# TM7705.net
KiCad netlist of a schematic drawn in Altium Designer
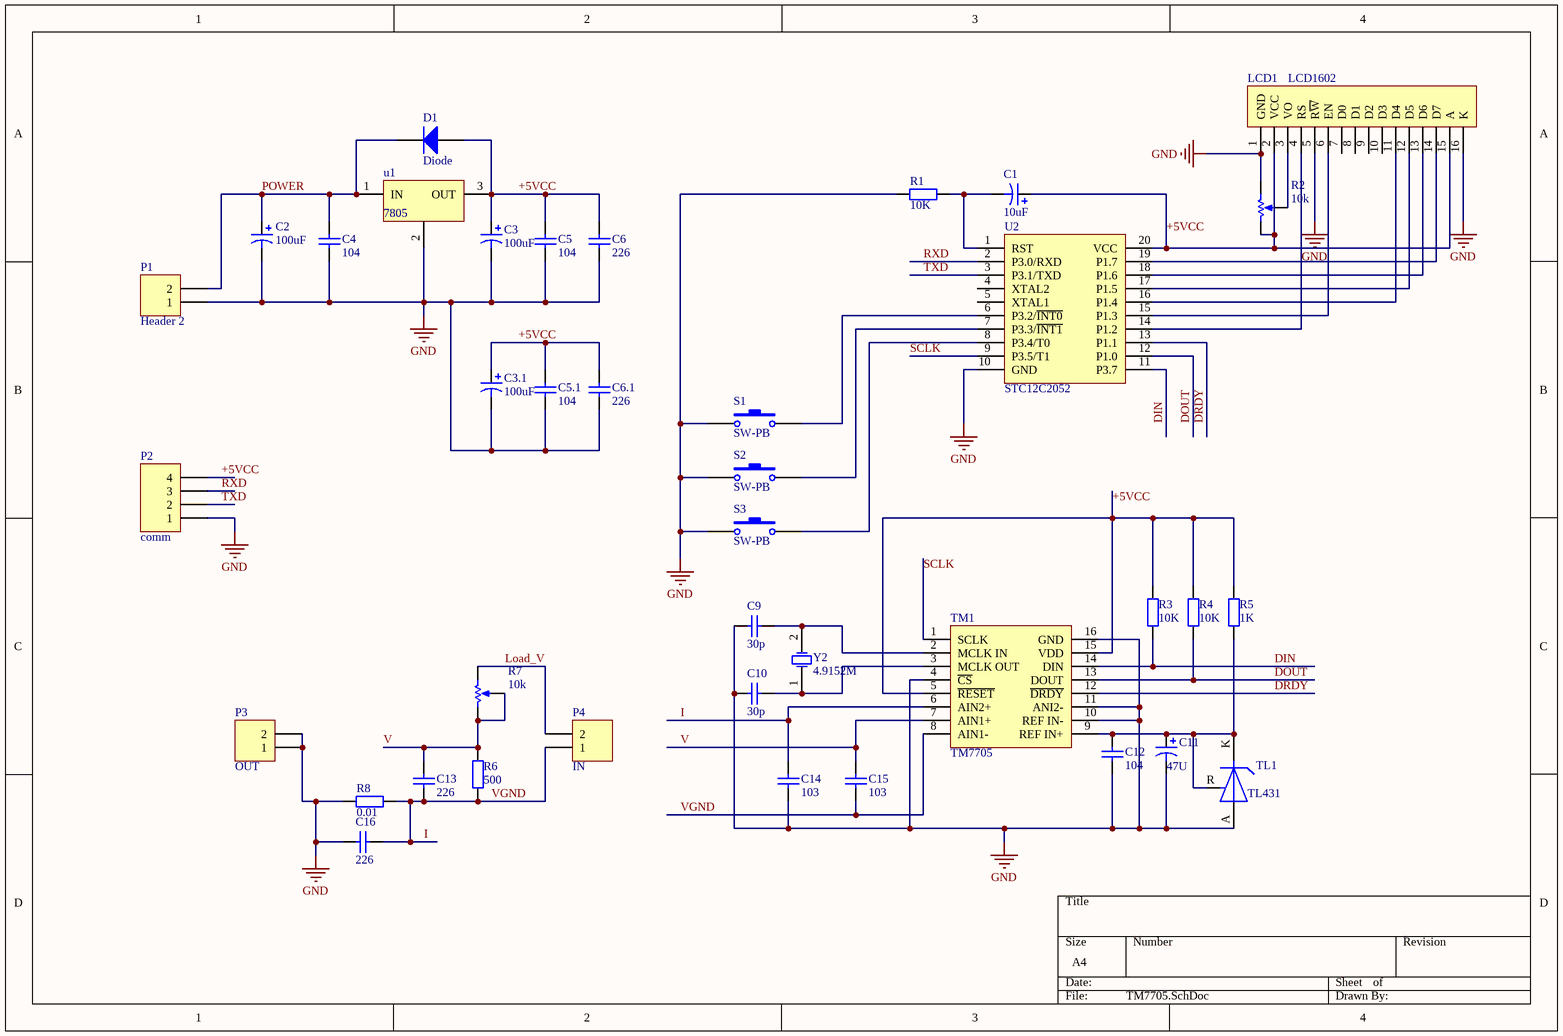
[diagram p0: TM7705.SchDoc]

(export (version "E")
  (design (tool "Eeschema 10.0.6"))
  (components
    (comp (ref "C1")
      (value "10uF")
      (footprint "0805")
      (description "Polarized Capacitor (Radial)")
      (fields (field (name "PUBLISHER") "Altium Limited"))
      (libsource (lib "Miscellaneous Devices") (part "Cap Pol1"))
    )
    (comp (ref "C2")
      (value "100uF")
      (footprint "DR3")
      (description "Polarized Capacitor (Radial)")
      (fields (field (name "PUBLISHER") "Altium Limited"))
      (libsource (lib "Miscellaneous Devices") (part "Cap Pol1"))
    )
    (comp (ref "C3")
      (value "100uF")
      (footprint "DR")
      (description "Polarized Capacitor (Radial)")
      (fields (field (name "PUBLISHER") "Altium Limited"))
      (libsource (lib "Miscellaneous Devices") (part "Cap Pol1"))
    )
    (comp (ref "C3.1")
      (value "100uF")
      (footprint "DR")
      (description "Polarized Capacitor (Radial)")
      (fields (field (name "PUBLISHER") "Altium Limited"))
      (libsource (lib "Miscellaneous Devices") (part "Cap Pol1"))
    )
    (comp (ref "C4")
      (value "104")
      (footprint "0805C")
      (description "Capacitor")
      (fields (field (name "PUBLISHER") "Altium Limited"))
      (libsource (lib "Miscellaneous Devices") (part "Cap"))
    )
    (comp (ref "C5")
      (value "104")
      (footprint "0805C")
      (description "Capacitor")
      (fields (field (name "PUBLISHER") "Altium Limited"))
      (libsource (lib "Miscellaneous Devices") (part "Cap"))
    )
    (comp (ref "C5.1")
      (value "104")
      (footprint "0805C")
      (description "Capacitor")
      (fields (field (name "PUBLISHER") "Altium Limited"))
      (libsource (lib "Miscellaneous Devices") (part "Cap"))
    )
    (comp (ref "C6")
      (value "226")
      (footprint "0805C")
      (description "Capacitor")
      (fields (field (name "PUBLISHER") "Altium Limited"))
      (libsource (lib "Miscellaneous Devices") (part "Cap"))
    )
    (comp (ref "C6.1")
      (value "226")
      (footprint "0805C")
      (description "Capacitor")
      (fields (field (name "PUBLISHER") "Altium Limited"))
      (libsource (lib "Miscellaneous Devices") (part "Cap"))
    )
    (comp (ref "C9")
      (value "30p")
      (footprint "0805C")
      (description "Capacitor")
      (fields (field (name "PUBLISHER") "Altium Limited"))
      (libsource (lib "Miscellaneous Devices") (part "Cap"))
    )
    (comp (ref "C10")
      (value "30p")
      (footprint "0805C")
      (description "Capacitor")
      (fields (field (name "PUBLISHER") "Altium Limited"))
      (libsource (lib "Miscellaneous Devices") (part "Cap"))
    )
    (comp (ref "C11")
      (value "47U")
      (footprint "DR")
      (description "Polarized Capacitor (Radial)")
      (fields (field (name "PUBLISHER") "Altium Limited"))
      (libsource (lib "Miscellaneous Devices") (part "Cap Pol1"))
    )
    (comp (ref "C12")
      (value "104")
      (footprint "0805C")
      (description "Capacitor")
      (fields (field (name "PUBLISHER") "Altium Limited"))
      (libsource (lib "Miscellaneous Devices") (part "Cap"))
    )
    (comp (ref "C13")
      (value "226")
      (footprint "0805C")
      (description "Capacitor")
      (fields (field (name "PUBLISHER") "Altium Limited"))
      (libsource (lib "Miscellaneous Devices") (part "Cap"))
    )
    (comp (ref "C14")
      (value "103")
      (footprint "0805C")
      (description "Capacitor")
      (fields (field (name "PUBLISHER") "Altium Limited"))
      (libsource (lib "Miscellaneous Devices") (part "Cap"))
    )
    (comp (ref "C15")
      (value "103")
      (footprint "0805C")
      (description "Capacitor")
      (fields (field (name "PUBLISHER") "Altium Limited"))
      (libsource (lib "Miscellaneous Devices") (part "Cap"))
    )
    (comp (ref "C16")
      (value "226")
      (footprint "0805C")
      (description "Capacitor")
      (fields (field (name "PUBLISHER") "Altium Limited"))
      (libsource (lib "Miscellaneous Devices") (part "Cap"))
    )
    (comp (ref "D1")
      (value "Diode")
      (footprint "DO-214AC")
      (description "Default Diode")
      (fields (field (name "PUBLISHER") "Altium Limited"))
      (libsource (lib "Miscellaneous Devices") (part "Diode"))
    )
    (comp (ref "LCD1") (value "LCD1602") (footprint "LCD1602") (libsource (lib "Sch库") (part "LCD1602")))
    (comp (ref "P1")
      (value "Header 2")
      (footprint "HDR1X2")
      (description "Header, 2-Pin")
      (fields (field (name "PUBLISHER") "Altium Limited"))
      (libsource (lib "Miscellaneous Connectors") (part "Header 2"))
    )
    (comp (ref "P2")
      (value "comm")
      (footprint "HDR1X4")
      (description "Header, 4-Pin")
      (fields (field (name "PUBLISHER") "Altium Limited"))
      (libsource (lib "Miscellaneous Connectors") (part "Header 4"))
    )
    (comp (ref "P3")
      (value "OUT")
      (footprint "HDR1X2")
      (description "Header, 2-Pin")
      (fields (field (name "PUBLISHER") "Altium Limited"))
      (libsource (lib "Miscellaneous Connectors") (part "Header 2"))
    )
    (comp (ref "P4")
      (value "IN")
      (footprint "HDR1X2")
      (description "Header, 2-Pin")
      (fields (field (name "PUBLISHER") "Altium Limited"))
      (libsource (lib "") (part "Header 2_1"))
    )
    (comp (ref "R1")
      (value "10K")
      (footprint "0805R")
      (description "Resistor")
      (fields (field (name "PUBLISHER") "Altium Limited"))
      (libsource (lib "") (part "Res2_1"))
    )
    (comp (ref "R2")
      (value "10k")
      (footprint "DWQ")
      (description "Potentiometer")
      (fields (field (name "PUBLISHER") "Altium Limited"))
      (libsource (lib "Miscellaneous Devices") (part "RPot"))
    )
    (comp (ref "R3")
      (value "10K")
      (footprint "0805R")
      (description "Resistor")
      (fields (field (name "PUBLISHER") "Altium Limited"))
      (libsource (lib "Miscellaneous Devices") (part "Res2"))
    )
    (comp (ref "R4")
      (value "10K")
      (footprint "0805R")
      (description "Resistor")
      (fields (field (name "PUBLISHER") "Altium Limited"))
      (libsource (lib "Miscellaneous Devices") (part "Res2"))
    )
    (comp (ref "R5")
      (value "1K")
      (footprint "0805R")
      (description "Resistor")
      (fields (field (name "PUBLISHER") "Altium Limited"))
      (libsource (lib "Miscellaneous Devices") (part "Res2"))
    )
    (comp (ref "R6")
      (value "500")
      (footprint "0805R")
      (description "Resistor")
      (fields (field (name "PUBLISHER") "Altium Limited"))
      (libsource (lib "") (part "Res2_2"))
    )
    (comp (ref "R7")
      (value "10k")
      (footprint "DWQ1")
      (description "Potentiometer")
      (fields (field (name "PUBLISHER") "Altium Limited"))
      (libsource (lib "Miscellaneous Devices") (part "RPot"))
    )
    (comp (ref "R8")
      (value "0.01")
      (footprint "DZ-1W")
      (description "Resistor")
      (fields (field (name "PUBLISHER") "Altium Limited"))
      (libsource (lib "") (part "Res2_1"))
    )
    (comp (ref "S1")
      (value "SW-PB")
      (footprint "SW")
      (description "Switch")
      (fields (field (name "PUBLISHER") "Altium Limited"))
      (libsource (lib "Miscellaneous Devices") (part "SW-PB"))
    )
    (comp (ref "S2")
      (value "SW-PB")
      (footprint "SW")
      (description "Switch")
      (fields (field (name "PUBLISHER") "Altium Limited"))
      (libsource (lib "Miscellaneous Devices") (part "SW-PB"))
    )
    (comp (ref "S3")
      (value "SW-PB")
      (footprint "SW")
      (description "Switch")
      (fields (field (name "PUBLISHER") "Altium Limited"))
      (libsource (lib "Miscellaneous Devices") (part "SW-PB"))
    )
    (comp (ref "TL1") (value "TL431") (footprint "TL431") (libsource (lib "Sch库") (part "TL431")))
    (comp (ref "TM1") (value "TM7705") (footprint "SOIC-16") (libsource (lib "Schlib1") (part "TM7705")))
    (comp (ref "u1") (value "7805") (footprint "DPAK") (libsource (lib "Schlib1") (part "7805")))
    (comp (ref "U2") (value "STC12C2052") (footprint "SOIC-20") (libsource (lib "Sch库") (part "STC12C2052")))
    (comp (ref "Y2")
      (value "4.9152M")
      (footprint "JZ")
      (description "Crystal Oscillator")
      (fields (field (name "PUBLISHER") "Altium Limited"))
      (libsource (lib "Miscellaneous Devices") (part "XTAL"))
    )
  )
  (nets
    (net (code "1") (name "/+5VCC") (class "Default")
      (node (ref "C1") (pin "1") (pinfunction "1_1") (pintype "passive"))
      (node (ref "C3") (pin "1") (pinfunction "1_1") (pintype "passive"))
      (node (ref "C3.1") (pin "1") (pinfunction "1_1") (pintype "passive"))
      (node (ref "C5") (pin "2") (pinfunction "2_2") (pintype "passive"))
      (node (ref "C5.1") (pin "2") (pinfunction "2_2") (pintype "passive"))
      (node (ref "C6") (pin "2") (pinfunction "2_2") (pintype "passive"))
      (node (ref "C6.1") (pin "2") (pinfunction "2_2") (pintype "passive"))
      (node (ref "D1") (pin "1") (pinfunction "A_1") (pintype "passive"))
      (node (ref "LCD1") (pin "15") (pinfunction "A_15") (pintype "passive"))
      (node (ref "LCD1") (pin "2") (pinfunction "VCC_2") (pintype "passive"))
      (node (ref "P2") (pin "4") (pinfunction "4_4") (pintype "passive"))
      (node (ref "R2") (pin "2") (pinfunction "BOT_2") (pintype "passive"))
      (node (ref "R3") (pin "2") (pinfunction "2_2") (pintype "passive"))
      (node (ref "R4") (pin "2") (pinfunction "2_2") (pintype "passive"))
      (node (ref "R5") (pin "2") (pinfunction "2_2") (pintype "passive"))
      (node (ref "TM1") (pin "15") (pinfunction "VDD_15") (pintype "passive"))
      (node (ref "TM1") (pin "5") (pinfunction "~{RESET}_5") (pintype "passive"))
      (node (ref "U2") (pin "20") (pinfunction "VCC_20") (pintype "passive"))
      (node (ref "u1") (pin "3") (pinfunction "OUT_3") (pintype "passive"))
    )
    (net (code "2") (name "/DIN") (class "Default")
      (node (ref "R3") (pin "1") (pinfunction "1_1") (pintype "passive"))
      (node (ref "TM1") (pin "14") (pinfunction "DIN_14") (pintype "passive"))
      (node (ref "U2") (pin "11") (pinfunction "P3.7_11") (pintype "passive"))
    )
    (net (code "3") (name "/DOUT") (class "Default")
      (node (ref "R4") (pin "1") (pinfunction "1_1") (pintype "passive"))
      (node (ref "TM1") (pin "13") (pinfunction "DOUT_13") (pintype "passive"))
      (node (ref "U2") (pin "12") (pinfunction "P1.0_12") (pintype "passive"))
    )
    (net (code "4") (name "/DRDY") (class "Default")
      (node (ref "TM1") (pin "12") (pinfunction "~{DRDY}_12") (pintype "passive"))
      (node (ref "U2") (pin "13") (pinfunction "P1.1_13") (pintype "passive"))
    )
    (net (code "5") (name "/I") (class "Default")
      (node (ref "C13") (pin "1") (pinfunction "1_1") (pintype "passive"))
      (node (ref "C14") (pin "2") (pinfunction "2_2") (pintype "passive"))
      (node (ref "C15") (pin "1") (pinfunction "1_1") (pintype "passive"))
      (node (ref "C16") (pin "1") (pinfunction "1_1") (pintype "passive"))
      (node (ref "P4") (pin "1") (pinfunction "1_1") (pintype "passive"))
      (node (ref "R6") (pin "1") (pinfunction "1_1") (pintype "passive"))
      (node (ref "R8") (pin "1") (pinfunction "1_1") (pintype "passive"))
      (node (ref "TM1") (pin "6") (pinfunction "AIN2+_6") (pintype "passive"))
      (node (ref "TM1") (pin "8") (pinfunction "AIN1-_8") (pintype "passive"))
    )
    (net (code "6") (name "/Load_V") (class "Default")
      (node (ref "P4") (pin "2") (pinfunction "2_2") (pintype "passive"))
      (node (ref "R7") (pin "1") (pinfunction "TOP_1") (pintype "passive"))
    )
    (net (code "7") (name "/POWER") (class "Default")
      (node (ref "C2") (pin "1") (pinfunction "1_1") (pintype "passive"))
      (node (ref "C4") (pin "2") (pinfunction "2_2") (pintype "passive"))
      (node (ref "D1") (pin "2") (pinfunction "K_2") (pintype "passive"))
      (node (ref "P1") (pin "2") (pinfunction "2_2") (pintype "passive"))
      (node (ref "u1") (pin "1") (pinfunction "IN_1") (pintype "passive"))
    )
    (net (code "8") (name "/RXD") (class "Default")
      (node (ref "P2") (pin "3") (pinfunction "3_3") (pintype "passive"))
      (node (ref "U2") (pin "2") (pinfunction "P3.0/RXD_2") (pintype "passive"))
    )
    (net (code "9") (name "/SCLK") (class "Default")
      (node (ref "TM1") (pin "1") (pinfunction "SCLK_1") (pintype "passive"))
      (node (ref "U2") (pin "9") (pinfunction "P3.5/T1_9") (pintype "passive"))
    )
    (net (code "10") (name "/TXD") (class "Default")
      (node (ref "P2") (pin "2") (pinfunction "2_2") (pintype "passive"))
      (node (ref "U2") (pin "3") (pinfunction "P3.1/TXD_3") (pintype "passive"))
    )
    (net (code "11") (name "/V") (class "Default")
      (node (ref "C13") (pin "2") (pinfunction "2_2") (pintype "passive"))
      (node (ref "C15") (pin "2") (pinfunction "2_2") (pintype "passive"))
      (node (ref "R6") (pin "2") (pinfunction "2_2") (pintype "passive"))
      (node (ref "R7") (pin "2") (pinfunction "BOT_2") (pintype "passive"))
      (node (ref "R7") (pin "3") (pinfunction "TAP_3") (pintype "passive"))
      (node (ref "TM1") (pin "7") (pinfunction "AIN1+_7") (pintype "passive"))
    )
    (net (code "12") (name "GND") (class "Default")
      (node (ref "C10") (pin "1") (pinfunction "1_1") (pintype "passive"))
      (node (ref "C11") (pin "2") (pinfunction "2_2") (pintype "passive"))
      (node (ref "C12") (pin "1") (pinfunction "1_1") (pintype "passive"))
      (node (ref "C14") (pin "1") (pinfunction "1_1") (pintype "passive"))
      (node (ref "C16") (pin "2") (pinfunction "2_2") (pintype "passive"))
      (node (ref "C2") (pin "2") (pinfunction "2_2") (pintype "passive"))
      (node (ref "C3") (pin "2") (pinfunction "2_2") (pintype "passive"))
      (node (ref "C3.1") (pin "2") (pinfunction "2_2") (pintype "passive"))
      (node (ref "C4") (pin "1") (pinfunction "1_1") (pintype "passive"))
      (node (ref "C5") (pin "1") (pinfunction "1_1") (pintype "passive"))
      (node (ref "C5.1") (pin "1") (pinfunction "1_1") (pintype "passive"))
      (node (ref "C6") (pin "1") (pinfunction "1_1") (pintype "passive"))
      (node (ref "C6.1") (pin "1") (pinfunction "1_1") (pintype "passive"))
      (node (ref "C9") (pin "1") (pinfunction "1_1") (pintype "passive"))
      (node (ref "LCD1") (pin "1") (pinfunction "GND_1") (pintype "passive"))
      (node (ref "LCD1") (pin "16") (pinfunction "K_16") (pintype "passive"))
      (node (ref "LCD1") (pin "5") (pinfunction "R~{W}_5") (pintype "passive"))
      (node (ref "P1") (pin "1") (pinfunction "1_1") (pintype "passive"))
      (node (ref "P2") (pin "1") (pinfunction "1_1") (pintype "passive"))
      (node (ref "P3") (pin "1") (pinfunction "1_1") (pintype "passive"))
      (node (ref "P3") (pin "2") (pinfunction "2_2") (pintype "passive"))
      (node (ref "R1") (pin "2") (pinfunction "2_2") (pintype "passive"))
      (node (ref "R2") (pin "1") (pinfunction "TOP_1") (pintype "passive"))
      (node (ref "R8") (pin "2") (pinfunction "2_2") (pintype "passive"))
      (node (ref "S1") (pin "1") (pinfunction "1_1") (pintype "passive"))
      (node (ref "S2") (pin "1") (pinfunction "1_1") (pintype "passive"))
      (node (ref "S3") (pin "1") (pinfunction "1_1") (pintype "passive"))
      (node (ref "TL1") (pin "A") (pinfunction "A_A") (pintype "passive"))
      (node (ref "TM1") (pin "10") (pinfunction "REF_IN-_10") (pintype "passive"))
      (node (ref "TM1") (pin "11") (pinfunction "ANI2-_11") (pintype "passive"))
      (node (ref "TM1") (pin "16") (pinfunction "GND_16") (pintype "passive"))
      (node (ref "TM1") (pin "4") (pinfunction "~{CS}_4") (pintype "passive"))
      (node (ref "U2") (pin "10") (pinfunction "GND_10") (pintype "passive"))
      (node (ref "u1") (pin "2") (pinfunction "GND_2") (pintype "passive"))
    )
    (net (code "13") (name "Net-(LCD1-D4)") (class "Default")
      (node (ref "LCD1") (pin "11") (pinfunction "D4_11") (pintype "passive"))
      (node (ref "U2") (pin "16") (pinfunction "P1.4_16") (pintype "passive"))
    )
    (net (code "14") (name "Net-(LCD1-D5)") (class "Default")
      (node (ref "LCD1") (pin "12") (pinfunction "D5_12") (pintype "passive"))
      (node (ref "U2") (pin "17") (pinfunction "P1.5_17") (pintype "passive"))
    )
    (net (code "15") (name "Net-(LCD1-D6)") (class "Default")
      (node (ref "LCD1") (pin "13") (pinfunction "D6_13") (pintype "passive"))
      (node (ref "U2") (pin "18") (pinfunction "P1.6_18") (pintype "passive"))
    )
    (net (code "16") (name "Net-(LCD1-D7)") (class "Default")
      (node (ref "LCD1") (pin "14") (pinfunction "D7_14") (pintype "passive"))
      (node (ref "U2") (pin "19") (pinfunction "P1.7_19") (pintype "passive"))
    )
    (net (code "17") (name "Net-(LCD1-EN)") (class "Default")
      (node (ref "LCD1") (pin "6") (pinfunction "EN_6") (pintype "passive"))
      (node (ref "U2") (pin "15") (pinfunction "P1.3_15") (pintype "passive"))
    )
    (net (code "18") (name "Net-(LCD1-RS)") (class "Default")
      (node (ref "LCD1") (pin "4") (pinfunction "RS_4") (pintype "passive"))
      (node (ref "U2") (pin "14") (pinfunction "P1.2_14") (pintype "passive"))
    )
    (net (code "19") (name "Net-(LCD1-VO)") (class "Default")
      (node (ref "LCD1") (pin "3") (pinfunction "VO_3") (pintype "passive"))
      (node (ref "R2") (pin "3") (pinfunction "TAP_3") (pintype "passive"))
    )
    (net (code "20") (name "Net-(TM1-MCLK_IN)") (class "Default")
      (node (ref "C9") (pin "2") (pinfunction "2_2") (pintype "passive"))
      (node (ref "TM1") (pin "2") (pinfunction "MCLK_IN_2") (pintype "passive"))
      (node (ref "Y2") (pin "2") (pinfunction "OSC2_2") (pintype "passive"))
    )
    (net (code "21") (name "Net-(TM1-MCLK_OUT)") (class "Default")
      (node (ref "C10") (pin "2") (pinfunction "2_2") (pintype "passive"))
      (node (ref "TM1") (pin "3") (pinfunction "MCLK_OUT_3") (pintype "passive"))
      (node (ref "Y2") (pin "1") (pinfunction "OSC1_1") (pintype "passive"))
    )
    (net (code "22") (name "Net-(TM1-REF_IN+)") (class "Default")
      (node (ref "C11") (pin "1") (pinfunction "1_1") (pintype "passive"))
      (node (ref "C12") (pin "2") (pinfunction "2_2") (pintype "passive"))
      (node (ref "R5") (pin "1") (pinfunction "1_1") (pintype "passive"))
      (node (ref "TL1") (pin "K") (pinfunction "K_K") (pintype "passive"))
      (node (ref "TL1") (pin "R") (pinfunction "R_R") (pintype "passive"))
      (node (ref "TM1") (pin "9") (pinfunction "REF_IN+_9") (pintype "passive"))
    )
    (net (code "23") (name "Net-(U2-P3.2{slash}~{INT0})") (class "Default")
      (node (ref "S1") (pin "2") (pinfunction "2_2") (pintype "passive"))
      (node (ref "U2") (pin "6") (pinfunction "P3.2/~{INT0}_6") (pintype "passive"))
    )
    (net (code "24") (name "Net-(U2-P3.3{slash}~{INT1})") (class "Default")
      (node (ref "S2") (pin "2") (pinfunction "2_2") (pintype "passive"))
      (node (ref "U2") (pin "7") (pinfunction "P3.3/~{INT1}_7") (pintype "passive"))
    )
    (net (code "25") (name "Net-(U2-P3.4{slash}T0)") (class "Default")
      (node (ref "S3") (pin "2") (pinfunction "2_2") (pintype "passive"))
      (node (ref "U2") (pin "8") (pinfunction "P3.4/T0_8") (pintype "passive"))
    )
    (net (code "26") (name "Net-(U2-RST)") (class "Default")
      (node (ref "C1") (pin "2") (pinfunction "2_2") (pintype "passive"))
      (node (ref "R1") (pin "1") (pinfunction "1_1") (pintype "passive"))
      (node (ref "U2") (pin "1") (pinfunction "RST_1") (pintype "passive"))
    )
    (net (code "27") (name "unconnected-(LCD1-D0-Pad7)") (class "Default")
      (node (ref "LCD1") (pin "7") (pinfunction "D0_7") (pintype "passive"))
    )
    (net (code "28") (name "unconnected-(LCD1-D1-Pad8)") (class "Default")
      (node (ref "LCD1") (pin "8") (pinfunction "D1_8") (pintype "passive"))
    )
    (net (code "29") (name "unconnected-(LCD1-D2-Pad9)") (class "Default")
      (node (ref "LCD1") (pin "9") (pinfunction "D2_9") (pintype "passive"))
    )
    (net (code "30") (name "unconnected-(LCD1-D3-Pad10)") (class "Default")
      (node (ref "LCD1") (pin "10") (pinfunction "D3_10") (pintype "passive"))
    )
    (net (code "31") (name "unconnected-(U2-XTAL1-Pad5)") (class "Default")
      (node (ref "U2") (pin "5") (pinfunction "XTAL1_5") (pintype "passive"))
    )
    (net (code "32") (name "unconnected-(U2-XTAL2-Pad4)") (class "Default")
      (node (ref "U2") (pin "4") (pinfunction "XTAL2_4") (pintype "passive"))
    )
  )
)
